# STM32H503CBT61_STM32H503CBT6.net
KiCad netlist of a schematic drawn in Altium Designer
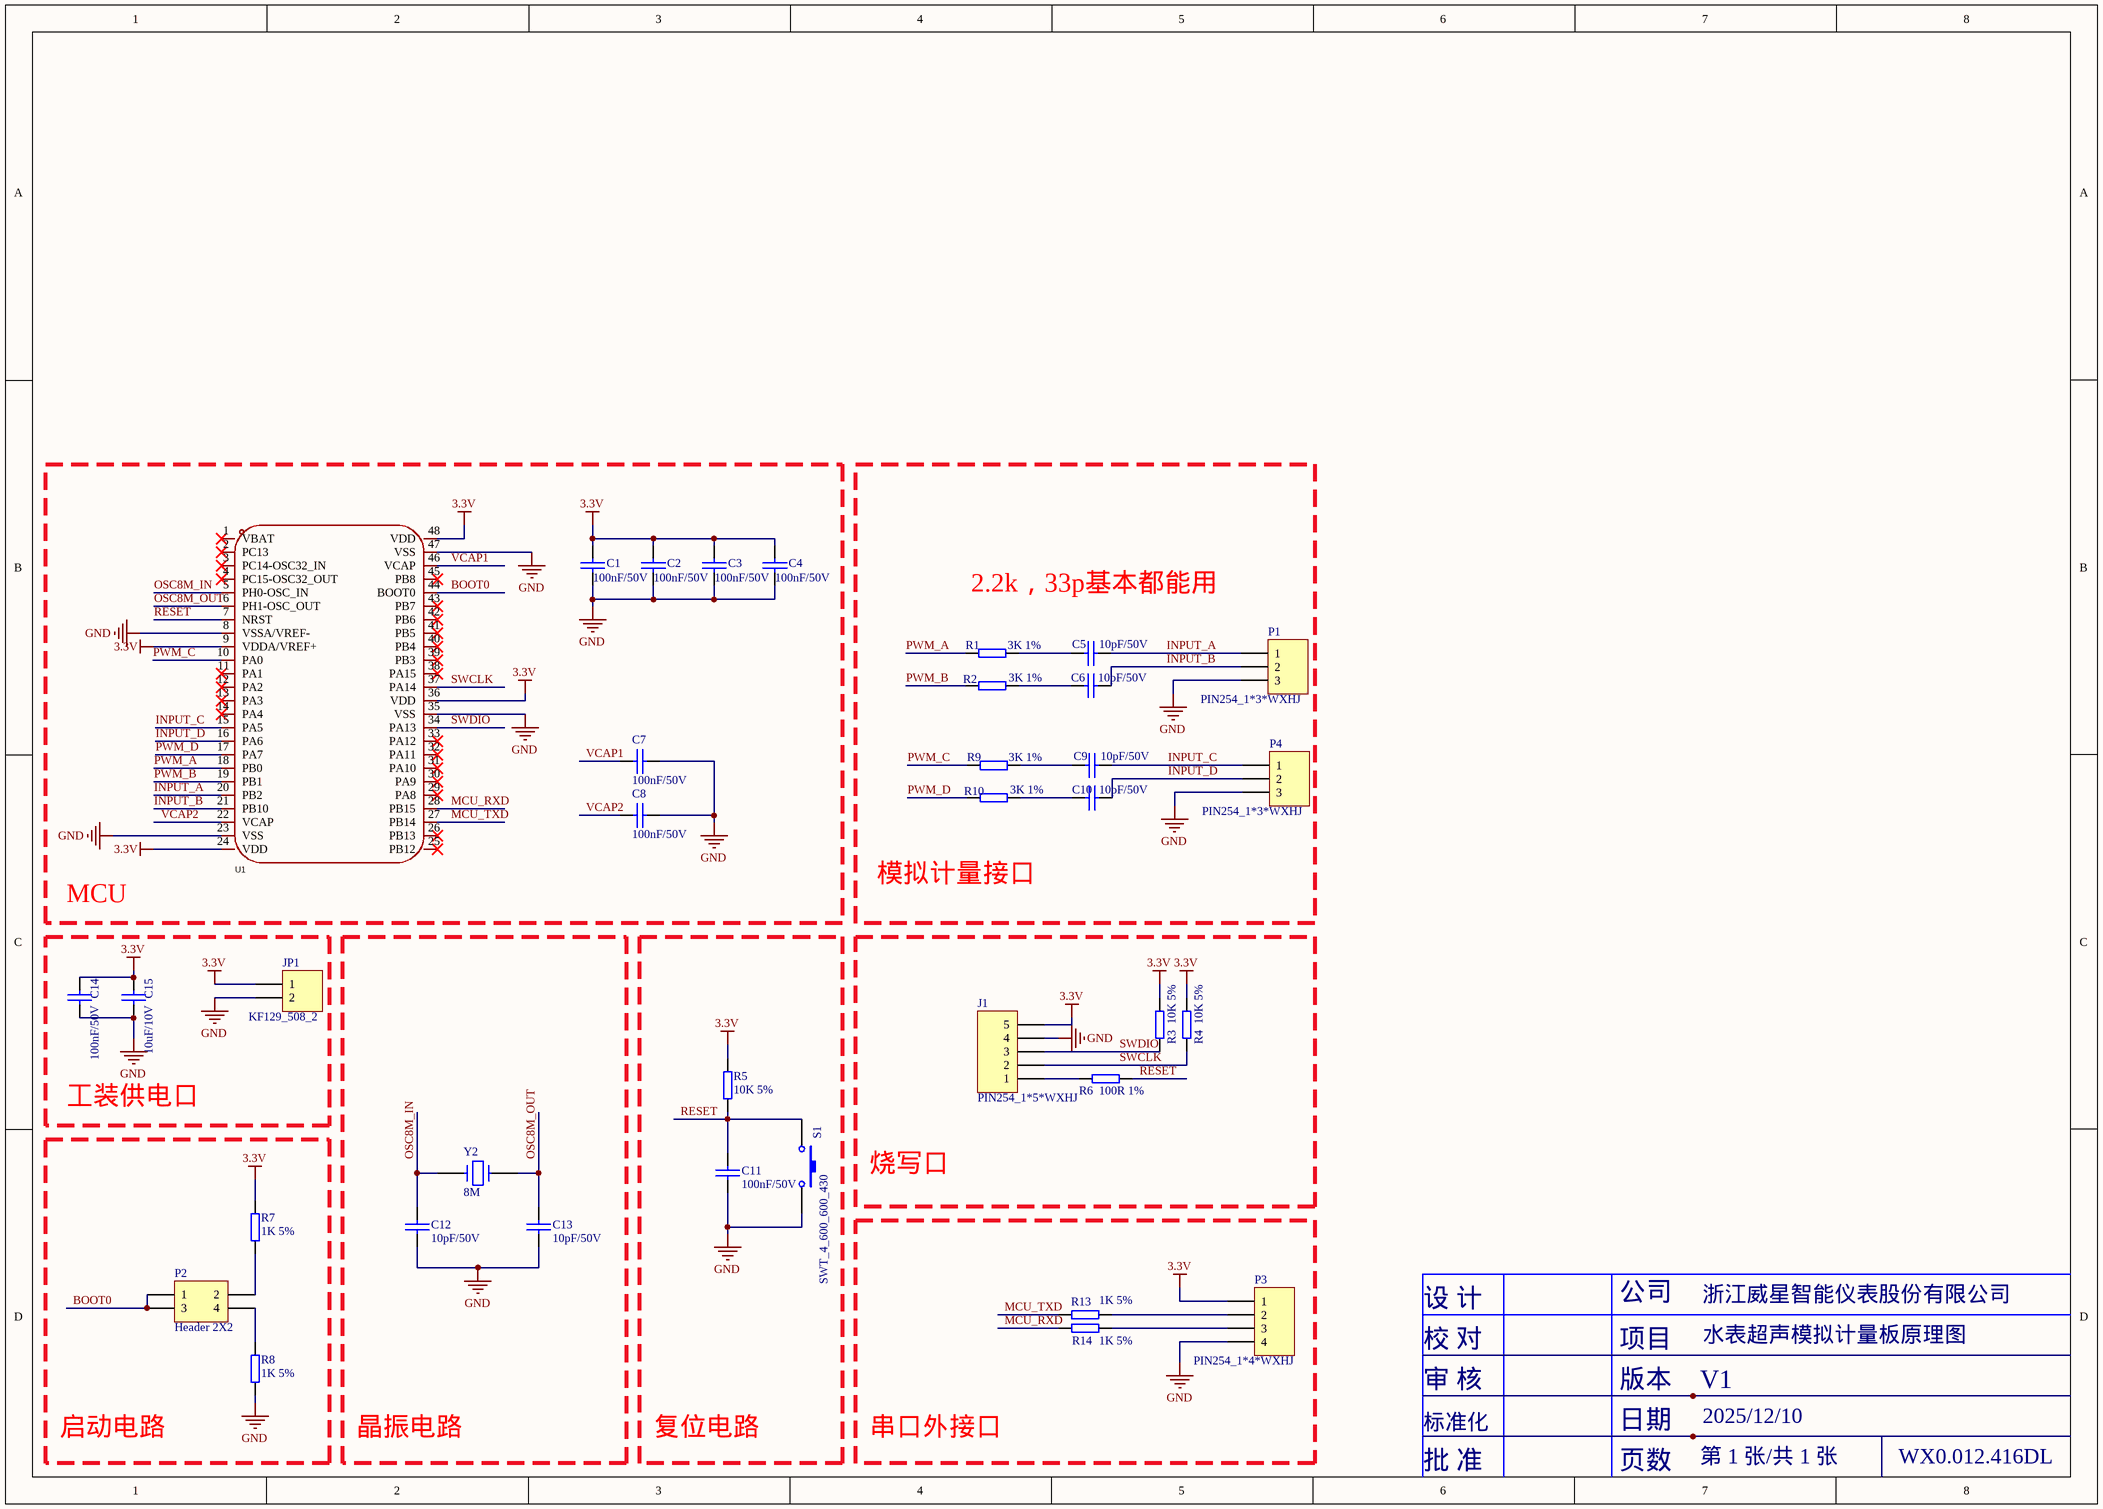
[diagram p0: STM32H503CBT61_STM32H503CBT6.schdoc]

(export (version "E")
  (design (tool "Eeschema 10.0.6"))
  (components
    (comp (ref "C1")
      (value "100nF/50V")
      (footprint "CAP0603")
      (description "104pF,50 V,±10%,0603,国巨,CC0603KRX7R9BB104")
      (fields (field (name "PART NUMBER") "101020103-0021"))
      (libsource (lib "Database_Libs2") (part "CC03K7R9_100N"))
    )
    (comp (ref "C2")
      (value "100nF/50V")
      (footprint "CAP0603")
      (description "104pF,50 V,±10%,0603,国巨,CC0603KRX7R9BB104")
      (fields (field (name "PART NUMBER") "101020103-0021"))
      (libsource (lib "Database_Libs2") (part "CC03K7R9_100N"))
    )
    (comp (ref "C3")
      (value "100nF/50V")
      (footprint "CAP0603")
      (description "104pF,50 V,±10%,0603,国巨,CC0603KRX7R9BB104")
      (fields (field (name "PART NUMBER") "101020103-0021"))
      (libsource (lib "Database_Libs2") (part "CC03K7R9_100N"))
    )
    (comp (ref "C4")
      (value "100nF/50V")
      (footprint "CAP0603")
      (description "104pF,50 V,±10%,0603,国巨,CC0603KRX7R9BB104")
      (fields (field (name "PART NUMBER") "101020103-0021"))
      (libsource (lib "Database_Libs2") (part "CC03K7R9_100N"))
    )
    (comp (ref "C5")
      (value "10pF/50V")
      (footprint "CAP0603")
      (description "33pF,50 V,±10%,0603,国巨,CC0603KRNPO9BN33")
      (fields (field (name "PART NUMBER") "101020103-0027"))
      (libsource (lib "Database_Libs2") (part "CC03KPO9_33P"))
    )
    (comp (ref "C6")
      (value "10pF/50V")
      (footprint "CAP0603")
      (description "33pF,50 V,±10%,0603,国巨,CC0603KRNPO9BN33")
      (fields (field (name "PART NUMBER") "101020103-0027"))
      (libsource (lib "Database_Libs2") (part "CC03KPO9_33P"))
    )
    (comp (ref "C7")
      (value "100nF/50V")
      (footprint "CAP0603")
      (description "104pF,50 V,±10%,0603,国巨,CC0603KRX7R9BB104")
      (fields (field (name "PART NUMBER") "101020103-0021"))
      (libsource (lib "Database_Libs2") (part "CC03K7R9_100N"))
    )
    (comp (ref "C8")
      (value "100nF/50V")
      (footprint "CAP0603")
      (description "104pF,50 V,±10%,0603,国巨,CC0603KRX7R9BB104")
      (fields (field (name "PART NUMBER") "101020103-0021"))
      (libsource (lib "Database_Libs2") (part "CC03K7R9_100N"))
    )
    (comp (ref "C9")
      (value "10pF/50V")
      (footprint "CAP0603")
      (description "33pF,50 V,±10%,0603,国巨,CC0603KRNPO9BN33")
      (fields (field (name "PART NUMBER") "101020103-0027"))
      (libsource (lib "Database_Libs2") (part "CC03KPO9_33P"))
    )
    (comp (ref "C10")
      (value "10pF/50V")
      (footprint "CAP0603")
      (description "33pF,50 V,±10%,0603,国巨,CC0603KRNPO9BN33")
      (fields (field (name "PART NUMBER") "101020103-0027"))
      (libsource (lib "Database_Libs2") (part "CC03KPO9_33P"))
    )
    (comp (ref "C11")
      (value "100nF/50V")
      (footprint "CAP0603")
      (description "104pF,50 V,±10%,0603,国巨,CC0603KRX7R9BB104")
      (fields (field (name "PART NUMBER") "101020103-0021"))
      (libsource (lib "Database_Libs2") (part "CC03K7R9_100N"))
    )
    (comp (ref "C12")
      (value "10pF/50V")
      (footprint "CAP0603")
      (description "10pF,50 V,±5%,0603,X7R,国巨,CC0603JRNPO9BN100")
      (fields (field (name "PART NUMBER") "101020103-0014"))
      (libsource (lib "Database_Libs2") (part "CC03JPO9_10P"))
    )
    (comp (ref "C13")
      (value "10pF/50V")
      (footprint "CAP0603")
      (description "10pF,50 V,±5%,0603,X7R,国巨,CC0603JRNPO9BN100")
      (fields (field (name "PART NUMBER") "101020103-0014"))
      (libsource (lib "Database_Libs2") (part "CC03JPO9_10P"))
    )
    (comp (ref "C14")
      (value "100nF/50V")
      (footprint "CAP0603")
      (description "104pF,50 V,±10%,0603,国巨,CC0603KRX7R9BB104")
      (fields (field (name "PART NUMBER") "101020103-0021"))
      (libsource (lib "Database_Libs2") (part "CC03K7R9_100N"))
    )
    (comp (ref "C15")
      (value "10uF/10V")
      (footprint "CAP0603")
      (description "106pF,10 V,±10%,0603,村田,GRM188R61A106KE47D")
      (fields (field (name "PART NUMBER") "101020103-0026"))
      (libsource (lib "Database_Libs2") (part "CC03K5R6_10U"))
    )
    (comp (ref "J1")
      (value "PIN254_1*5*WXHJ")
      (footprint "PIN254_1*5*1100S")
      (description "1*5 ，Φ1.0 ，2.54mm，直脚,无需焊接器件")
      (fields (field (name "PART NUMBER") "AD_WXHJ_PinHeader_02"))
      (libsource (lib "模拟计量") (part "PIN254_1*5*1100S"))
    )
    (comp (ref "JP1")
      (value "KF129_508_2")
      (footprint "KF129_508_2")
      (description "KF129-2P,螺丝紧固,2,ABS,松涛")
      (fields (field (name "PART NUMBER") "1010904-0015"))
      (libsource (lib "模拟计量") (part "KF129_508_2"))
    )
    (comp (ref "P1")
      (value "PIN254_1*3*WXHJ")
      (footprint "PIN254_1*3*1100S - duplicate")
      (description "1*3 ，Φ1.0 ，2.54mm，直脚,无需焊接器件")
      (fields (field (name "PART NUMBER") "AD_WXHJ_PinHeader_01"))
      (libsource (lib "模拟计量") (part "PIN254_1*3*1100S"))
    )
    (comp (ref "P2")
      (value "Header 2X2")
      (footprint "HDR2X2")
      (description "Header, 4-Pin, Dual row")
      (libsource (lib "模拟计量") (part "Header 2X2"))
    )
    (comp (ref "P3")
      (value "PIN254_1*4*WXHJ")
      (footprint "PIN254_1*4*1100S")
      (description "1*4 ，Φ1.0 ，2.54mm，直脚,无需焊接器件")
      (fields (field (name "PART NUMBER") "AD_WXHJ_PinHeader_01"))
      (libsource (lib "模拟计量") (part "PIN254_1*4*1100S"))
    )
    (comp (ref "P4")
      (value "PIN254_1*3*WXHJ")
      (footprint "PIN254_1*3*1100S - duplicate")
      (description "1*3 ，Φ1.0 ，2.54mm，直脚,无需焊接器件")
      (fields (field (name "PART NUMBER") "AD_WXHJ_PinHeader_01"))
      (libsource (lib "模拟计量") (part "PIN254_1*3*1100S"))
    )
    (comp (ref "R1")
      (value "3K 1%")
      (footprint "RES0603")
      (description "3.3K±1%,1/10W,0603")
      (fields (field (name "PART NUMBER") "101010103-0059"))
      (libsource (lib "Database_Libs2") (part "RC03F_3.3K"))
    )
    (comp (ref "R2")
      (value "3K 1%")
      (footprint "RES0603")
      (description "3.3K±1%,1/10W,0603")
      (fields (field (name "PART NUMBER") "101010103-0059"))
      (libsource (lib "Database_Libs2") (part "RC03F_3.3K"))
    )
    (comp (ref "R3")
      (value "10K 5%")
      (footprint "RES0603")
      (description "国巨,±5%,0603,,155 ℃,-55 ℃,RC0603JR-0710KL,无铅,200 ppm/℃,1/10W,,10K")
      (fields (field (name "PART NUMBER") "101010103-0003"))
      (libsource (lib "Database_Libs2") (part "RC03J_10K"))
    )
    (comp (ref "R4")
      (value "10K 5%")
      (footprint "RES0603")
      (description "国巨,±5%,0603,,155 ℃,-55 ℃,RC0603JR-0710KL,无铅,200 ppm/℃,1/10W,,10K")
      (fields (field (name "PART NUMBER") "101010103-0003"))
      (libsource (lib "Database_Libs2") (part "RC03J_10K"))
    )
    (comp (ref "R5")
      (value "10K 5%")
      (footprint "RES0603")
      (description "国巨,±5%,0603,,155 ℃,-55 ℃,RC0603JR-0710KL,无铅,200 ppm/℃,1/10W,,10K")
      (fields (field (name "PART NUMBER") "101010103-0003"))
      (libsource (lib "Database_Libs2") (part "RC03J_10K"))
    )
    (comp (ref "R6")
      (value "100R 1%")
      (footprint "RES0603")
      (description "100Ω,±1%,1/10W,0603,国巨股份有限公司,RC0603FR-07100RL")
      (fields (field (name "PART NUMBER") "101010103-0041"))
      (libsource (lib "Database_Libs2") (part "RC03J_100R"))
    )
    (comp (ref "R7")
      (value "1K 5%")
      (footprint "RES0603")
      (description "1K,±5%,1/10W,0603,国巨,RC0603JR-071KL")
      (fields (field (name "PART NUMBER") "101010103-0008"))
      (libsource (lib "Database_Libs2") (part "RC03J_1K"))
    )
    (comp (ref "R8")
      (value "1K 5%")
      (footprint "RES0603")
      (description "1K,±5%,1/10W,0603,国巨,RC0603JR-071KL")
      (fields (field (name "PART NUMBER") "101010103-0008"))
      (libsource (lib "Database_Libs2") (part "RC03J_1K"))
    )
    (comp (ref "R9")
      (value "3K 1%")
      (footprint "RES0603")
      (description "3.3K±1%,1/10W,0603")
      (fields (field (name "PART NUMBER") "101010103-0059"))
      (libsource (lib "Database_Libs2") (part "RC03F_3.3K"))
    )
    (comp (ref "R10")
      (value "3K 1%")
      (footprint "RES0603")
      (description "3.3K±1%,1/10W,0603")
      (fields (field (name "PART NUMBER") "101010103-0059"))
      (libsource (lib "Database_Libs2") (part "RC03F_3.3K"))
    )
    (comp (ref "R13")
      (value "1K 5%")
      (footprint "RES0603")
      (description "1K,±5%,1/10W,0603,国巨,RC0603JR-071KL")
      (fields (field (name "PART NUMBER") "101010103-0008"))
      (libsource (lib "Database_Libs2") (part "RC03J_1K"))
    )
    (comp (ref "R14")
      (value "1K 5%")
      (footprint "RES0603")
      (description "1K,±5%,1/10W,0603,国巨,RC0603JR-071KL")
      (fields (field (name "PART NUMBER") "101010103-0008"))
      (libsource (lib "Database_Libs2") (part "RC03J_1K"))
    )
    (comp (ref "S1")
      (value "SWT_4_600_600_430")
      (footprint "SWT_4_600_600")
      (description "TS-1102,机械轻触,6*6*4.3直插,6*6*4.3直插,乐清市羽欧电子")
      (fields (field (name "PART NUMBER") "1011001-0027"))
      (libsource (lib "Database_Libs2") (part "07_SWT_4_600_600_430"))
    )
    (comp (ref "U1")
      (value "STM32H503CBT6")
      (footprint "LQFP-48")
      (fields (field (name "MANUFACTURER") "ST(意法半导体)"))
      (libsource (lib "altium-import") (part "root_0_STM32H503CBT6_"))
    )
    (comp (ref "Y2")
      (value "8M")
      (footprint "HC-49S")
      (description "8M,HC-49,8M,100 ppm/℃,无源,红星,8M无源晶振")
      (fields (field (name "PART NUMBER") "1010601-0007"))
      (libsource (lib "Database_Libs2") (part "04_XTALTA10SF_8ME"))
    )
  )
  (nets
    (net (code "1") (name "/BOOT0") (class "Default")
      (node (ref "P2") (pin "1") (pinfunction "1_1") (pintype "passive"))
      (node (ref "P2") (pin "3") (pinfunction "3_3") (pintype "passive"))
      (node (ref "U1") (pin "44") (pinfunction "BOOT0_44") (pintype "passive"))
    )
    (net (code "2") (name "/INPUT_A") (class "Default")
      (node (ref "C5") (pin "2") (pinfunction "2_2") (pintype "passive"))
      (node (ref "P1") (pin "1") (pinfunction "1_1") (pintype "passive"))
      (node (ref "U1") (pin "20") (pinfunction "PB2_20") (pintype "passive"))
    )
    (net (code "3") (name "/INPUT_B") (class "Default")
      (node (ref "C6") (pin "2") (pinfunction "2_2") (pintype "passive"))
      (node (ref "P1") (pin "2") (pinfunction "2_2") (pintype "passive"))
      (node (ref "U1") (pin "21") (pinfunction "PB10_21") (pintype "passive"))
    )
    (net (code "4") (name "/INPUT_C") (class "Default")
      (node (ref "C9") (pin "2") (pinfunction "2_2") (pintype "passive"))
      (node (ref "P4") (pin "1") (pinfunction "1_1") (pintype "passive"))
      (node (ref "U1") (pin "15") (pinfunction "PA5_15") (pintype "passive"))
    )
    (net (code "5") (name "/INPUT_D") (class "Default")
      (node (ref "C10") (pin "2") (pinfunction "2_2") (pintype "passive"))
      (node (ref "P4") (pin "2") (pinfunction "2_2") (pintype "passive"))
      (node (ref "U1") (pin "16") (pinfunction "PA6_16") (pintype "passive"))
    )
    (net (code "6") (name "/MCU_RXD") (class "Default")
      (node (ref "R14") (pin "1") (pinfunction "1_1") (pintype "passive"))
      (node (ref "U1") (pin "28") (pinfunction "PB15_28") (pintype "passive"))
    )
    (net (code "7") (name "/MCU_TXD") (class "Default")
      (node (ref "R13") (pin "1") (pinfunction "1_1") (pintype "passive"))
      (node (ref "U1") (pin "27") (pinfunction "PB14_27") (pintype "passive"))
    )
    (net (code "8") (name "/OSC8M_IN") (class "Default")
      (node (ref "C12") (pin "1") (pinfunction "1_1") (pintype "passive"))
      (node (ref "U1") (pin "5") (pinfunction "PH0-OSC_IN_5") (pintype "passive"))
      (node (ref "Y2") (pin "1") (pinfunction "1_1") (pintype "passive"))
    )
    (net (code "9") (name "/OSC8M_OUT") (class "Default")
      (node (ref "C13") (pin "1") (pinfunction "1_1") (pintype "passive"))
      (node (ref "U1") (pin "6") (pinfunction "PH1-OSC_OUT_6") (pintype "passive"))
      (node (ref "Y2") (pin "2") (pinfunction "2_2") (pintype "passive"))
    )
    (net (code "10") (name "/PWM_A") (class "Default")
      (node (ref "R1") (pin "1") (pinfunction "1_1") (pintype "passive"))
      (node (ref "U1") (pin "18") (pinfunction "PB0_18") (pintype "passive"))
    )
    (net (code "11") (name "/PWM_B") (class "Default")
      (node (ref "R2") (pin "1") (pinfunction "1_1") (pintype "passive"))
      (node (ref "U1") (pin "19") (pinfunction "PB1_19") (pintype "passive"))
    )
    (net (code "12") (name "/PWM_C") (class "Default")
      (node (ref "R9") (pin "1") (pinfunction "1_1") (pintype "passive"))
      (node (ref "U1") (pin "10") (pinfunction "PA0_10") (pintype "passive"))
    )
    (net (code "13") (name "/PWM_D") (class "Default")
      (node (ref "R10") (pin "1") (pinfunction "1_1") (pintype "passive"))
      (node (ref "U1") (pin "17") (pinfunction "PA7_17") (pintype "passive"))
    )
    (net (code "14") (name "/RESET") (class "Default")
      (node (ref "C11") (pin "1") (pinfunction "1_1") (pintype "passive"))
      (node (ref "R5") (pin "1") (pinfunction "1_1") (pintype "passive"))
      (node (ref "R6") (pin "2") (pinfunction "2_2") (pintype "passive"))
      (node (ref "S1") (pin "1") (pinfunction "1_1") (pintype "passive"))
      (node (ref "U1") (pin "7") (pinfunction "NRST_7") (pintype "passive"))
    )
    (net (code "15") (name "/SWCLK") (class "Default")
      (node (ref "J1") (pin "2") (pinfunction "2_2") (pintype "passive"))
      (node (ref "R4") (pin "2") (pinfunction "2_2") (pintype "passive"))
      (node (ref "U1") (pin "37") (pinfunction "PA14_37") (pintype "passive"))
    )
    (net (code "16") (name "/SWDIO") (class "Default")
      (node (ref "J1") (pin "3") (pinfunction "3_3") (pintype "passive"))
      (node (ref "R3") (pin "2") (pinfunction "2_2") (pintype "passive"))
      (node (ref "U1") (pin "34") (pinfunction "PA13_34") (pintype "passive"))
    )
    (net (code "17") (name "/VCAP1") (class "Default")
      (node (ref "C7") (pin "1") (pinfunction "1_1") (pintype "passive"))
      (node (ref "U1") (pin "46") (pinfunction "VCAP_46") (pintype "passive"))
    )
    (net (code "18") (name "/VCAP2") (class "Default")
      (node (ref "C8") (pin "2") (pinfunction "2_2") (pintype "passive"))
      (node (ref "U1") (pin "22") (pinfunction "VCAP_22") (pintype "passive"))
    )
    (net (code "19") (name "3.3V") (class "Default")
      (node (ref "C1") (pin "1") (pinfunction "1_1") (pintype "passive"))
      (node (ref "C14") (pin "1") (pinfunction "1_1") (pintype "passive"))
      (node (ref "C15") (pin "1") (pinfunction "1_1") (pintype "passive"))
      (node (ref "C2") (pin "1") (pinfunction "1_1") (pintype "passive"))
      (node (ref "C3") (pin "1") (pinfunction "1_1") (pintype "passive"))
      (node (ref "C4") (pin "1") (pinfunction "1_1") (pintype "passive"))
      (node (ref "J1") (pin "5") (pinfunction "5_5") (pintype "passive"))
      (node (ref "JP1") (pin "1") (pinfunction "1_1") (pintype "passive"))
      (node (ref "P3") (pin "1") (pinfunction "1_1") (pintype "passive"))
      (node (ref "R3") (pin "1") (pinfunction "1_1") (pintype "passive"))
      (node (ref "R4") (pin "1") (pinfunction "1_1") (pintype "passive"))
      (node (ref "R5") (pin "2") (pinfunction "2_2") (pintype "passive"))
      (node (ref "R7") (pin "2") (pinfunction "2_2") (pintype "passive"))
      (node (ref "U1") (pin "24") (pinfunction "VDD_24") (pintype "passive"))
      (node (ref "U1") (pin "36") (pinfunction "VDD_36") (pintype "passive"))
      (node (ref "U1") (pin "48") (pinfunction "VDD_48") (pintype "passive"))
      (node (ref "U1") (pin "9") (pinfunction "VDDA/VREF+_9") (pintype "passive"))
    )
    (net (code "20") (name "GND") (class "Default")
      (node (ref "C1") (pin "2") (pinfunction "2_2") (pintype "passive"))
      (node (ref "C11") (pin "2") (pinfunction "2_2") (pintype "passive"))
      (node (ref "C12") (pin "2") (pinfunction "2_2") (pintype "passive"))
      (node (ref "C13") (pin "2") (pinfunction "2_2") (pintype "passive"))
      (node (ref "C14") (pin "2") (pinfunction "2_2") (pintype "passive"))
      (node (ref "C15") (pin "2") (pinfunction "2_2") (pintype "passive"))
      (node (ref "C2") (pin "2") (pinfunction "2_2") (pintype "passive"))
      (node (ref "C3") (pin "2") (pinfunction "2_2") (pintype "passive"))
      (node (ref "C4") (pin "2") (pinfunction "2_2") (pintype "passive"))
      (node (ref "C7") (pin "2") (pinfunction "2_2") (pintype "passive"))
      (node (ref "C8") (pin "1") (pinfunction "1_1") (pintype "passive"))
      (node (ref "J1") (pin "4") (pinfunction "4_4") (pintype "passive"))
      (node (ref "JP1") (pin "2") (pinfunction "2_2") (pintype "passive"))
      (node (ref "P1") (pin "3") (pinfunction "3_3") (pintype "passive"))
      (node (ref "P3") (pin "4") (pinfunction "4_4") (pintype "passive"))
      (node (ref "P4") (pin "3") (pinfunction "3_3") (pintype "passive"))
      (node (ref "R8") (pin "1") (pinfunction "1_1") (pintype "passive"))
      (node (ref "S1") (pin "2") (pinfunction "2_2") (pintype "passive"))
      (node (ref "U1") (pin "23") (pinfunction "VSS_23") (pintype "passive"))
      (node (ref "U1") (pin "35") (pinfunction "VSS_35") (pintype "passive"))
      (node (ref "U1") (pin "47") (pinfunction "VSS_47") (pintype "passive"))
      (node (ref "U1") (pin "8") (pinfunction "VSSA/VREF-_8") (pintype "passive"))
    )
    (net (code "21") (name "Net-(C5-Pad1)") (class "Default")
      (node (ref "C5") (pin "1") (pinfunction "1_1") (pintype "passive"))
      (node (ref "R1") (pin "2") (pinfunction "2_2") (pintype "passive"))
    )
    (net (code "22") (name "Net-(C6-Pad1)") (class "Default")
      (node (ref "C6") (pin "1") (pinfunction "1_1") (pintype "passive"))
      (node (ref "R2") (pin "2") (pinfunction "2_2") (pintype "passive"))
    )
    (net (code "23") (name "Net-(C9-Pad1)") (class "Default")
      (node (ref "C9") (pin "1") (pinfunction "1_1") (pintype "passive"))
      (node (ref "R9") (pin "2") (pinfunction "2_2") (pintype "passive"))
    )
    (net (code "24") (name "Net-(C10-Pad1)") (class "Default")
      (node (ref "C10") (pin "1") (pinfunction "1_1") (pintype "passive"))
      (node (ref "R10") (pin "2") (pinfunction "2_2") (pintype "passive"))
    )
    (net (code "25") (name "Net-(J1-Pad1)") (class "Default")
      (node (ref "J1") (pin "1") (pinfunction "1_1") (pintype "passive"))
      (node (ref "R6") (pin "1") (pinfunction "1_1") (pintype "passive"))
    )
    (net (code "26") (name "Net-(P2-Pad2)") (class "Default")
      (node (ref "P2") (pin "2") (pinfunction "2_2") (pintype "passive"))
      (node (ref "R7") (pin "1") (pinfunction "1_1") (pintype "passive"))
    )
    (net (code "27") (name "Net-(P2-Pad4)") (class "Default")
      (node (ref "P2") (pin "4") (pinfunction "4_4") (pintype "passive"))
      (node (ref "R8") (pin "2") (pinfunction "2_2") (pintype "passive"))
    )
    (net (code "28") (name "Net-(P3-Pad2)") (class "Default")
      (node (ref "P3") (pin "2") (pinfunction "2_2") (pintype "passive"))
      (node (ref "R13") (pin "2") (pinfunction "2_2") (pintype "passive"))
    )
    (net (code "29") (name "Net-(P3-Pad3)") (class "Default")
      (node (ref "P3") (pin "3") (pinfunction "3_3") (pintype "passive"))
      (node (ref "R14") (pin "2") (pinfunction "2_2") (pintype "passive"))
    )
    (net (code "30") (name "unconnected-(U1-PA1-Pad11)") (class "Default")
      (node (ref "U1") (pin "11") (pinfunction "PA1_11") (pintype "passive+no_connect"))
    )
    (net (code "31") (name "unconnected-(U1-PA2-Pad12)") (class "Default")
      (node (ref "U1") (pin "12") (pinfunction "PA2_12") (pintype "passive+no_connect"))
    )
    (net (code "32") (name "unconnected-(U1-PA3-Pad13)") (class "Default")
      (node (ref "U1") (pin "13") (pinfunction "PA3_13") (pintype "passive+no_connect"))
    )
    (net (code "33") (name "unconnected-(U1-PA4-Pad14)") (class "Default")
      (node (ref "U1") (pin "14") (pinfunction "PA4_14") (pintype "passive+no_connect"))
    )
    (net (code "34") (name "unconnected-(U1-PA8-Pad29)") (class "Default")
      (node (ref "U1") (pin "29") (pinfunction "PA8_29") (pintype "passive+no_connect"))
    )
    (net (code "35") (name "unconnected-(U1-PA9-Pad30)") (class "Default")
      (node (ref "U1") (pin "30") (pinfunction "PA9_30") (pintype "passive+no_connect"))
    )
    (net (code "36") (name "unconnected-(U1-PA10-Pad31)") (class "Default")
      (node (ref "U1") (pin "31") (pinfunction "PA10_31") (pintype "passive+no_connect"))
    )
    (net (code "37") (name "unconnected-(U1-PA11-Pad32)") (class "Default")
      (node (ref "U1") (pin "32") (pinfunction "PA11_32") (pintype "passive+no_connect"))
    )
    (net (code "38") (name "unconnected-(U1-PA12-Pad33)") (class "Default")
      (node (ref "U1") (pin "33") (pinfunction "PA12_33") (pintype "passive+no_connect"))
    )
    (net (code "39") (name "unconnected-(U1-PA15-Pad38)") (class "Default")
      (node (ref "U1") (pin "38") (pinfunction "PA15_38") (pintype "passive+no_connect"))
    )
    (net (code "40") (name "unconnected-(U1-PB3-Pad39)") (class "Default")
      (node (ref "U1") (pin "39") (pinfunction "PB3_39") (pintype "passive+no_connect"))
    )
    (net (code "41") (name "unconnected-(U1-PB4-Pad40)") (class "Default")
      (node (ref "U1") (pin "40") (pinfunction "PB4_40") (pintype "passive+no_connect"))
    )
    (net (code "42") (name "unconnected-(U1-PB5-Pad41)") (class "Default")
      (node (ref "U1") (pin "41") (pinfunction "PB5_41") (pintype "passive+no_connect"))
    )
    (net (code "43") (name "unconnected-(U1-PB6-Pad42)") (class "Default")
      (node (ref "U1") (pin "42") (pinfunction "PB6_42") (pintype "passive+no_connect"))
    )
    (net (code "44") (name "unconnected-(U1-PB7-Pad43)") (class "Default")
      (node (ref "U1") (pin "43") (pinfunction "PB7_43") (pintype "passive+no_connect"))
    )
    (net (code "45") (name "unconnected-(U1-PB8-Pad45)") (class "Default")
      (node (ref "U1") (pin "45") (pinfunction "PB8_45") (pintype "passive+no_connect"))
    )
    (net (code "46") (name "unconnected-(U1-PB12-Pad25)") (class "Default")
      (node (ref "U1") (pin "25") (pinfunction "PB12_25") (pintype "passive+no_connect"))
    )
    (net (code "47") (name "unconnected-(U1-PB13-Pad26)") (class "Default")
      (node (ref "U1") (pin "26") (pinfunction "PB13_26") (pintype "passive+no_connect"))
    )
    (net (code "48") (name "unconnected-(U1-PC13-Pad2)") (class "Default")
      (node (ref "U1") (pin "2") (pinfunction "PC13_2") (pintype "passive+no_connect"))
    )
    (net (code "49") (name "unconnected-(U1-PC14-OSC32_IN-Pad3)") (class "Default")
      (node (ref "U1") (pin "3") (pinfunction "PC14-OSC32_IN_3") (pintype "passive+no_connect"))
    )
    (net (code "50") (name "unconnected-(U1-PC15-OSC32_OUT-Pad4)") (class "Default")
      (node (ref "U1") (pin "4") (pinfunction "PC15-OSC32_OUT_4") (pintype "passive+no_connect"))
    )
    (net (code "51") (name "unconnected-(U1-VBAT-Pad1)") (class "Default")
      (node (ref "U1") (pin "1") (pinfunction "VBAT_1") (pintype "passive+no_connect"))
    )
  )
)
